# RcMPPT-IO.net
KiCad netlist of a schematic drawn in Altium Designer
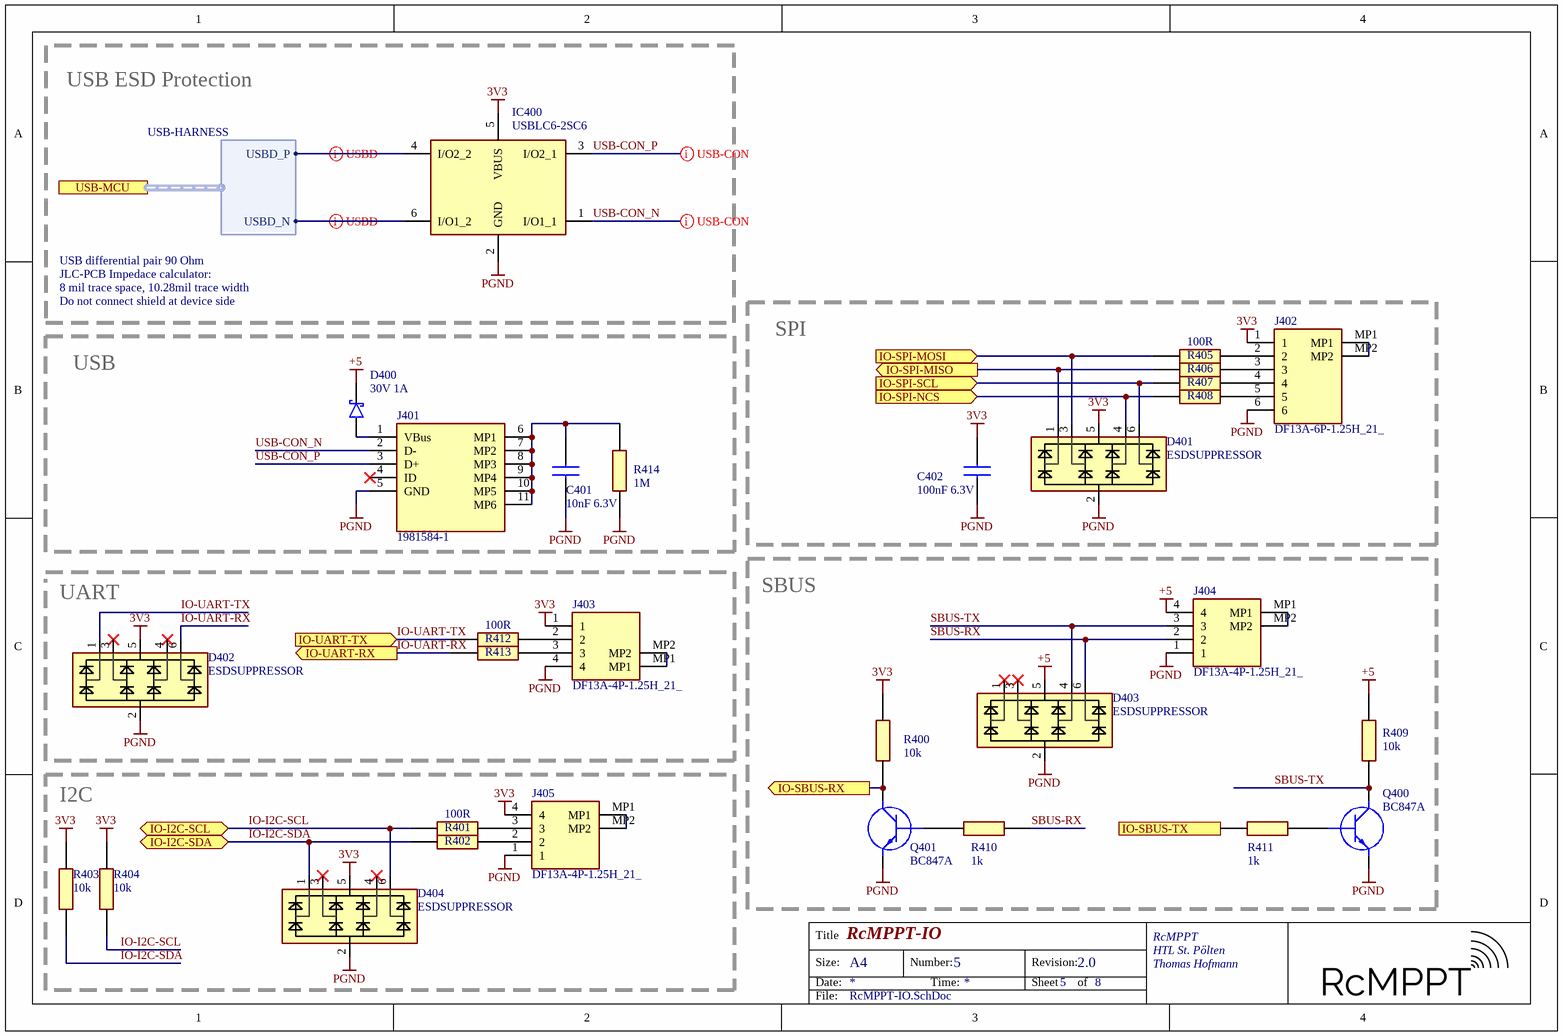
[diagram p0: RcMPPT-IO.SchDoc]

(export (version "E")
  (design (tool "Eeschema 10.0.6"))
  (components
    (comp (ref "C401")
      (value "10nF 6.3V")
      (footprint "CAPC1608X97N")
      (description "Capacitor")
      (libsource (lib "RcMPPTLib") (part "C0603"))
    )
    (comp (ref "C402")
      (value "100nF 6.3V")
      (footprint "CAPC1608X97N")
      (description "Capacitor")
      (libsource (lib "RcMPPTLib") (part "C0603"))
    )
    (comp (ref "D400")
      (value "30V 1A")
      (footprint "SOD-323")
      (description "Schottky Diode")
      (libsource (lib "RcMPPTLib") (part "SCHOTTKY-DIODE"))
    )
    (comp (ref "D401")
      (value "ESDSUPPRESSOR")
      (footprint "SOT23-6")
      (description "TVS Diode Array")
      (libsource (lib "RcMPPTLib") (part "ESDSUPPRESSOR"))
    )
    (comp (ref "D402")
      (value "ESDSUPPRESSOR")
      (footprint "SOT23-6")
      (description "TVS Diode Array")
      (libsource (lib "RcMPPTLib") (part "ESDSUPPRESSOR"))
    )
    (comp (ref "D403")
      (value "ESDSUPPRESSOR")
      (footprint "SOT23-6")
      (description "TVS Diode Array")
      (libsource (lib "RcMPPTLib") (part "ESDSUPPRESSOR"))
    )
    (comp (ref "D404")
      (value "ESDSUPPRESSOR")
      (footprint "SOT23-6")
      (description "TVS Diode Array")
      (libsource (lib "RcMPPTLib") (part "ESDSUPPRESSOR"))
    )
    (comp (ref "IC400")
      (value "USBLC6-2SC6")
      (footprint "SOT95P280X145-6N")
      (description "Integrated Circuit")
      (fields (field (name "MOUSER PART NUMBER") "511-USBLC6-2SC6"))
      (libsource (lib "RcMPPTLib") (part "USBLC6-2SC6"))
    )
    (comp (ref "J401")
      (value "1981584-1")
      (footprint "19815841")
      (description "Connector")
      (fields (field (name "MOUSER PART NUMBER") "571-1981584-1"))
      (libsource (lib "RcMPPTLib") (part "1981584-1"))
    )
    (comp (ref "J402")
      (value "DF13A-6P-1.25H_21_")
      (footprint "DF13A6P125H21")
      (description "Connector")
      (fields
        (field (name "MANUFACTURER_PART_NUMBER") "DF13A-6P-1.25H(21)")
        (field (name "MOUSER PART NUMBER") "798-DF13A6P125H21")
      )
      (libsource (lib "RcMPPTLib") (part "DF13A-6P-1.25H_21_"))
    )
    (comp (ref "J403")
      (value "DF13A-4P-1.25H_21_")
      (footprint "DF13A4P125H21")
      (description "Connector")
      (fields
        (field (name "MANUFACTURER_PART_NUMBER") "DF13A-4P-1.25H(21)")
        (field (name "MOUSER PART NUMBER") "798-DF13A4P125H21")
      )
      (libsource (lib "") (part "DF13A-4P-1.25H_21__1"))
    )
    (comp (ref "J404")
      (value "DF13A-4P-1.25H_21_")
      (footprint "DF13A4P125H21")
      (description "Connector")
      (fields
        (field (name "MANUFACTURER_PART_NUMBER") "DF13A-4P-1.25H(21)")
        (field (name "MOUSER PART NUMBER") "798-DF13A4P125H21")
      )
      (libsource (lib "RcMPPTLib") (part "DF13A-4P-1.25H_21_"))
    )
    (comp (ref "J405")
      (value "DF13A-4P-1.25H_21_")
      (footprint "DF13A4P125H21")
      (description "Connector")
      (fields
        (field (name "MANUFACTURER_PART_NUMBER") "DF13A-4P-1.25H(21)")
        (field (name "MOUSER PART NUMBER") "798-DF13A4P125H21")
      )
      (libsource (lib "RcMPPTLib") (part "DF13A-4P-1.25H_21_"))
    )
    (comp (ref "Q400")
      (value "BC847A")
      (footprint "SOT95P230X110-3N")
      (description "Transistor BJT NPN")
      (fields
        (field (name "MANUFACTURER_PART_NUMBER") "BC847A,235")
        (field (name "MOUSER PART NUMBER") "771-BC847A235")
      )
      (libsource (lib "RcMPPTLib") (part "BC847A,235"))
    )
    (comp (ref "Q401")
      (value "BC847A")
      (footprint "SOT95P230X110-3N")
      (description "Transistor BJT NPN")
      (fields
        (field (name "MANUFACTURER_PART_NUMBER") "BC847A,235")
        (field (name "MOUSER PART NUMBER") "771-BC847A235")
      )
      (libsource (lib "RcMPPTLib") (part "BC847A,235"))
    )
    (comp (ref "R400")
      (value "10k")
      (footprint "RESC1608X50N")
      (description "Resistor")
      (libsource (lib "") (part "R0603_2"))
    )
    (comp (ref "R401")
      (value "100R")
      (footprint "RESC1005X40N")
      (description "Resistor")
      (libsource (lib "RcMPPTLib") (part "R0402"))
    )
    (comp (ref "R402")
      (value "100R")
      (footprint "RESC1005X40N")
      (description "Resistor")
      (libsource (lib "RcMPPTLib") (part "R0402"))
    )
    (comp (ref "R403")
      (value "10k")
      (footprint "RESC1608X50N")
      (description "Resistor")
      (libsource (lib "RcMPPTLib") (part "R0603"))
    )
    (comp (ref "R404")
      (value "10k")
      (footprint "RESC1608X50N")
      (description "Resistor")
      (libsource (lib "RcMPPTLib") (part "R0603"))
    )
    (comp (ref "R405")
      (value "100R")
      (footprint "RESC1005X40N")
      (description "Resistor")
      (libsource (lib "RcMPPTLib") (part "R0402"))
    )
    (comp (ref "R406")
      (value "100R")
      (footprint "RESC1005X40N")
      (description "Resistor")
      (libsource (lib "RcMPPTLib") (part "R0402"))
    )
    (comp (ref "R407")
      (value "100R")
      (footprint "RESC1005X40N")
      (description "Resistor")
      (libsource (lib "RcMPPTLib") (part "R0402"))
    )
    (comp (ref "R408")
      (value "100R")
      (footprint "RESC1005X40N")
      (description "Resistor")
      (libsource (lib "RcMPPTLib") (part "R0402"))
    )
    (comp (ref "R409")
      (value "10k")
      (footprint "RESC1608X50N")
      (description "Resistor")
      (libsource (lib "") (part "R0603_1"))
    )
    (comp (ref "R410")
      (value "1k")
      (footprint "RESC1608X50N")
      (description "Resistor")
      (libsource (lib "") (part "R0603_1"))
    )
    (comp (ref "R411")
      (value "1k")
      (footprint "RESC1608X50N")
      (description "Resistor")
      (libsource (lib "RcMPPTLib") (part "R0603"))
    )
    (comp (ref "R412")
      (value "100R")
      (footprint "RESC1005X40N")
      (description "Resistor")
      (libsource (lib "RcMPPTLib") (part "R0402"))
    )
    (comp (ref "R413")
      (value "100R")
      (footprint "RESC1005X40N")
      (description "Resistor")
      (libsource (lib "RcMPPTLib") (part "R0402"))
    )
    (comp (ref "R414")
      (value "1M")
      (footprint "RESC1608X50N")
      (description "Resistor")
      (libsource (lib "") (part "R0603_2"))
    )
  )
  (nets
    (net (code "2") (name "+5") (class "Default")
      (node (ref "D400") (pin "1") (pinfunction "K_1") (pintype "passive"))
      (node (ref "D403") (pin "5") (pinfunction "VDD_5") (pintype "passive"))
      (node (ref "J404") (pin "4") (pinfunction "4_4") (pintype "passive"))
      (node (ref "R409") (pin "2") (pinfunction "2_2") (pintype "passive"))
    )
    (net (code "3") (name "/IO-I2C-SCL") (class "Default")
      (node (ref "D404") (pin "6") (pinfunction "CH4_6") (pintype "passive"))
      (node (ref "R401") (pin "1") (pinfunction "1_1") (pintype "passive"))
      (node (ref "R404") (pin "2") (pinfunction "2_2") (pintype "passive"))
    )
    (net (code "4") (name "/IO-I2C-SDA") (class "Default")
      (node (ref "D404") (pin "1") (pinfunction "CH1_1") (pintype "passive"))
      (node (ref "R402") (pin "1") (pinfunction "1_1") (pintype "passive"))
      (node (ref "R403") (pin "2") (pinfunction "2_2") (pintype "passive"))
    )
    (net (code "5") (name "/IO-SBUS-RX") (class "Default")
      (node (ref "Q401") (pin "3") (pinfunction "C_3") (pintype "passive"))
      (node (ref "R400") (pin "1") (pinfunction "1_1") (pintype "passive"))
    )
    (net (code "6") (name "/IO-SBUS-TX") (class "Default")
      (node (ref "R411") (pin "2") (pinfunction "2_2") (pintype "passive"))
    )
    (net (code "7") (name "/IO-SPI-MISO") (class "Default")
      (node (ref "D401") (pin "1") (pinfunction "CH1_1") (pintype "passive"))
      (node (ref "R406") (pin "1") (pinfunction "1_1") (pintype "passive"))
    )
    (net (code "8") (name "/IO-SPI-MOSI") (class "Default")
      (node (ref "D401") (pin "3") (pinfunction "CH2_3") (pintype "passive"))
      (node (ref "R405") (pin "1") (pinfunction "1_1") (pintype "passive"))
    )
    (net (code "9") (name "/IO-SPI-NCS") (class "Default")
      (node (ref "D401") (pin "4") (pinfunction "CH3_4") (pintype "passive"))
      (node (ref "R408") (pin "1") (pinfunction "1_1") (pintype "passive"))
    )
    (net (code "10") (name "/IO-SPI-SCL") (class "Default")
      (node (ref "D401") (pin "6") (pinfunction "CH4_6") (pintype "passive"))
      (node (ref "R407") (pin "1") (pinfunction "1_1") (pintype "passive"))
    )
    (net (code "11") (name "/IO-UART-RX") (class "Default")
      (node (ref "D402") (pin "6") (pinfunction "CH4_6") (pintype "passive"))
      (node (ref "R413") (pin "1") (pinfunction "1_1") (pintype "passive"))
    )
    (net (code "12") (name "/IO-UART-TX") (class "Default")
      (node (ref "D402") (pin "1") (pinfunction "CH1_1") (pintype "passive"))
      (node (ref "R412") (pin "1") (pinfunction "1_1") (pintype "passive"))
    )
    (net (code "13") (name "/SBUS-RX") (class "Default")
      (node (ref "D403") (pin "6") (pinfunction "CH4_6") (pintype "passive"))
      (node (ref "J404") (pin "2") (pinfunction "2_2") (pintype "passive"))
      (node (ref "R410") (pin "2") (pinfunction "2_2") (pintype "passive"))
    )
    (net (code "14") (name "/SBUS-TX") (class "Default")
      (node (ref "D403") (pin "4") (pinfunction "CH3_4") (pintype "passive"))
      (node (ref "J404") (pin "3") (pinfunction "3_3") (pintype "passive"))
      (node (ref "Q400") (pin "3") (pinfunction "C_3") (pintype "passive"))
      (node (ref "R409") (pin "1") (pinfunction "1_1") (pintype "passive"))
    )
    (net (code "15") (name "/USB-CON_N") (class "Default")
      (node (ref "IC400") (pin "1") (pinfunction "I/O1_1_1") (pintype "passive"))
      (node (ref "J401") (pin "2") (pinfunction "D-_2") (pintype "passive"))
    )
    (net (code "16") (name "/USB-CON_P") (class "Default")
      (node (ref "IC400") (pin "3") (pinfunction "I/O2_1_3") (pintype "passive"))
      (node (ref "J401") (pin "3") (pinfunction "D+_3") (pintype "passive"))
    )
    (net (code "17") (name "/USBD_N") (class "Default")
      (node (ref "IC400") (pin "6") (pinfunction "I/O1_2_6") (pintype "passive"))
    )
    (net (code "18") (name "/USBD_P") (class "Default")
      (node (ref "IC400") (pin "4") (pinfunction "I/O2_2_4") (pintype "passive"))
    )
    (net (code "20") (name "3V3") (class "Default")
      (node (ref "C402") (pin "2") (pinfunction "2_2") (pintype "passive"))
      (node (ref "D401") (pin "5") (pinfunction "VDD_5") (pintype "passive"))
      (node (ref "D402") (pin "5") (pinfunction "VDD_5") (pintype "passive"))
      (node (ref "D404") (pin "5") (pinfunction "VDD_5") (pintype "passive"))
      (node (ref "IC400") (pin "5") (pinfunction "VBUS_5") (pintype "passive"))
      (node (ref "J402") (pin "1") (pinfunction "1_1") (pintype "passive"))
      (node (ref "J403") (pin "1") (pinfunction "1_1") (pintype "passive"))
      (node (ref "J405") (pin "4") (pinfunction "4_4") (pintype "passive"))
      (node (ref "R400") (pin "2") (pinfunction "2_2") (pintype "passive"))
      (node (ref "R403") (pin "1") (pinfunction "1_1") (pintype "passive"))
      (node (ref "R404") (pin "1") (pinfunction "1_1") (pintype "passive"))
    )
    (net (code "21") (name "Net-(D400-A)") (class "Default")
      (node (ref "D400") (pin "2") (pinfunction "A_2") (pintype "passive"))
      (node (ref "J401") (pin "1") (pinfunction "VBus_1") (pintype "passive"))
    )
    (net (code "22") (name "Net-(J401-MP1)") (class "Default")
      (node (ref "C401") (pin "2") (pinfunction "2_2") (pintype "passive"))
      (node (ref "J401") (pin "10") (pinfunction "MP5_10") (pintype "passive"))
      (node (ref "J401") (pin "11") (pinfunction "MP6_11") (pintype "passive"))
      (node (ref "J401") (pin "6") (pinfunction "MP1_6") (pintype "passive"))
      (node (ref "J401") (pin "7") (pinfunction "MP2_7") (pintype "passive"))
      (node (ref "J401") (pin "8") (pinfunction "MP3_8") (pintype "passive"))
      (node (ref "J401") (pin "9") (pinfunction "MP4_9") (pintype "passive"))
      (node (ref "R414") (pin "2") (pinfunction "2_2") (pintype "passive"))
    )
    (net (code "23") (name "Net-(J402-Pad2)") (class "Default")
      (node (ref "J402") (pin "2") (pinfunction "2_2") (pintype "passive"))
      (node (ref "R405") (pin "2") (pinfunction "2_2") (pintype "passive"))
    )
    (net (code "24") (name "Net-(J402-Pad3)") (class "Default")
      (node (ref "J402") (pin "3") (pinfunction "3_3") (pintype "passive"))
      (node (ref "R406") (pin "2") (pinfunction "2_2") (pintype "passive"))
    )
    (net (code "25") (name "Net-(J402-Pad4)") (class "Default")
      (node (ref "J402") (pin "4") (pinfunction "4_4") (pintype "passive"))
      (node (ref "R407") (pin "2") (pinfunction "2_2") (pintype "passive"))
    )
    (net (code "26") (name "Net-(J402-Pad5)") (class "Default")
      (node (ref "J402") (pin "5") (pinfunction "5_5") (pintype "passive"))
      (node (ref "R408") (pin "2") (pinfunction "2_2") (pintype "passive"))
    )
    (net (code "27") (name "Net-(J402-PadMP1)") (class "Default")
      (node (ref "J402") (pin "MP1") (pinfunction "MP1_MP1") (pintype "passive"))
      (node (ref "J402") (pin "MP2") (pinfunction "MP2_MP2") (pintype "passive"))
    )
    (net (code "28") (name "Net-(J403-Pad2)") (class "Default")
      (node (ref "J403") (pin "2") (pinfunction "2_2") (pintype "passive"))
      (node (ref "R412") (pin "2") (pinfunction "2_2") (pintype "passive"))
    )
    (net (code "29") (name "Net-(J403-Pad3)") (class "Default")
      (node (ref "J403") (pin "3") (pinfunction "3_3") (pintype "passive"))
      (node (ref "R413") (pin "2") (pinfunction "2_2") (pintype "passive"))
    )
    (net (code "30") (name "Net-(J403-PadMP1)") (class "Default")
      (node (ref "J403") (pin "MP1") (pinfunction "MP1_MP1") (pintype "passive"))
      (node (ref "J403") (pin "MP2") (pinfunction "MP2_MP2") (pintype "passive"))
    )
    (net (code "31") (name "Net-(J404-PadMP1)") (class "Default")
      (node (ref "J404") (pin "MP1") (pinfunction "MP1_MP1") (pintype "passive"))
      (node (ref "J404") (pin "MP2") (pinfunction "MP2_MP2") (pintype "passive"))
    )
    (net (code "32") (name "Net-(J405-Pad2)") (class "Default")
      (node (ref "J405") (pin "2") (pinfunction "2_2") (pintype "passive"))
      (node (ref "R402") (pin "2") (pinfunction "2_2") (pintype "passive"))
    )
    (net (code "33") (name "Net-(J405-Pad3)") (class "Default")
      (node (ref "J405") (pin "3") (pinfunction "3_3") (pintype "passive"))
      (node (ref "R401") (pin "2") (pinfunction "2_2") (pintype "passive"))
    )
    (net (code "34") (name "Net-(J405-PadMP1)") (class "Default")
      (node (ref "J405") (pin "MP1") (pinfunction "MP1_MP1") (pintype "passive"))
      (node (ref "J405") (pin "MP2") (pinfunction "MP2_MP2") (pintype "passive"))
    )
    (net (code "35") (name "Net-(Q400-B)") (class "Default")
      (node (ref "Q400") (pin "1") (pinfunction "B_1") (pintype "passive"))
      (node (ref "R411") (pin "1") (pinfunction "1_1") (pintype "passive"))
    )
    (net (code "36") (name "Net-(Q401-B)") (class "Default")
      (node (ref "Q401") (pin "1") (pinfunction "B_1") (pintype "passive"))
      (node (ref "R410") (pin "1") (pinfunction "1_1") (pintype "passive"))
    )
    (net (code "37") (name "PGND") (class "Default")
      (node (ref "C401") (pin "1") (pinfunction "1_1") (pintype "passive"))
      (node (ref "C402") (pin "1") (pinfunction "1_1") (pintype "passive"))
      (node (ref "D401") (pin "2") (pinfunction "GND_2") (pintype "passive"))
      (node (ref "D402") (pin "2") (pinfunction "GND_2") (pintype "passive"))
      (node (ref "D403") (pin "2") (pinfunction "GND_2") (pintype "passive"))
      (node (ref "D404") (pin "2") (pinfunction "GND_2") (pintype "passive"))
      (node (ref "IC400") (pin "2") (pinfunction "GND_2") (pintype "passive"))
      (node (ref "J401") (pin "5") (pinfunction "GND_5") (pintype "passive"))
      (node (ref "J402") (pin "6") (pinfunction "6_6") (pintype "passive"))
      (node (ref "J403") (pin "4") (pinfunction "4_4") (pintype "passive"))
      (node (ref "J404") (pin "1") (pinfunction "1_1") (pintype "passive"))
      (node (ref "J405") (pin "1") (pinfunction "1_1") (pintype "passive"))
      (node (ref "Q400") (pin "2") (pinfunction "E_2") (pintype "passive"))
      (node (ref "Q401") (pin "2") (pinfunction "E_2") (pintype "passive"))
      (node (ref "R414") (pin "1") (pinfunction "1_1") (pintype "passive"))
    )
    (net (code "38") (name "unconnected-(D402-CH2-Pad3)") (class "Default")
      (node (ref "D402") (pin "3") (pinfunction "CH2_3") (pintype "passive+no_connect"))
    )
    (net (code "39") (name "unconnected-(D402-CH3-Pad4)") (class "Default")
      (node (ref "D402") (pin "4") (pinfunction "CH3_4") (pintype "passive+no_connect"))
    )
    (net (code "40") (name "unconnected-(D403-CH1-Pad1)") (class "Default")
      (node (ref "D403") (pin "1") (pinfunction "CH1_1") (pintype "passive+no_connect"))
    )
    (net (code "41") (name "unconnected-(D403-CH2-Pad3)") (class "Default")
      (node (ref "D403") (pin "3") (pinfunction "CH2_3") (pintype "passive+no_connect"))
    )
    (net (code "42") (name "unconnected-(D404-CH2-Pad3)") (class "Default")
      (node (ref "D404") (pin "3") (pinfunction "CH2_3") (pintype "passive+no_connect"))
    )
    (net (code "43") (name "unconnected-(D404-CH3-Pad4)") (class "Default")
      (node (ref "D404") (pin "4") (pinfunction "CH3_4") (pintype "passive+no_connect"))
    )
    (net (code "44") (name "unconnected-(J401-ID-Pad4)") (class "Default")
      (node (ref "J401") (pin "4") (pinfunction "ID_4") (pintype "passive+no_connect"))
    )
  )
)
